# Inductive.net
KiCad netlist of a schematic drawn in Altium Designer
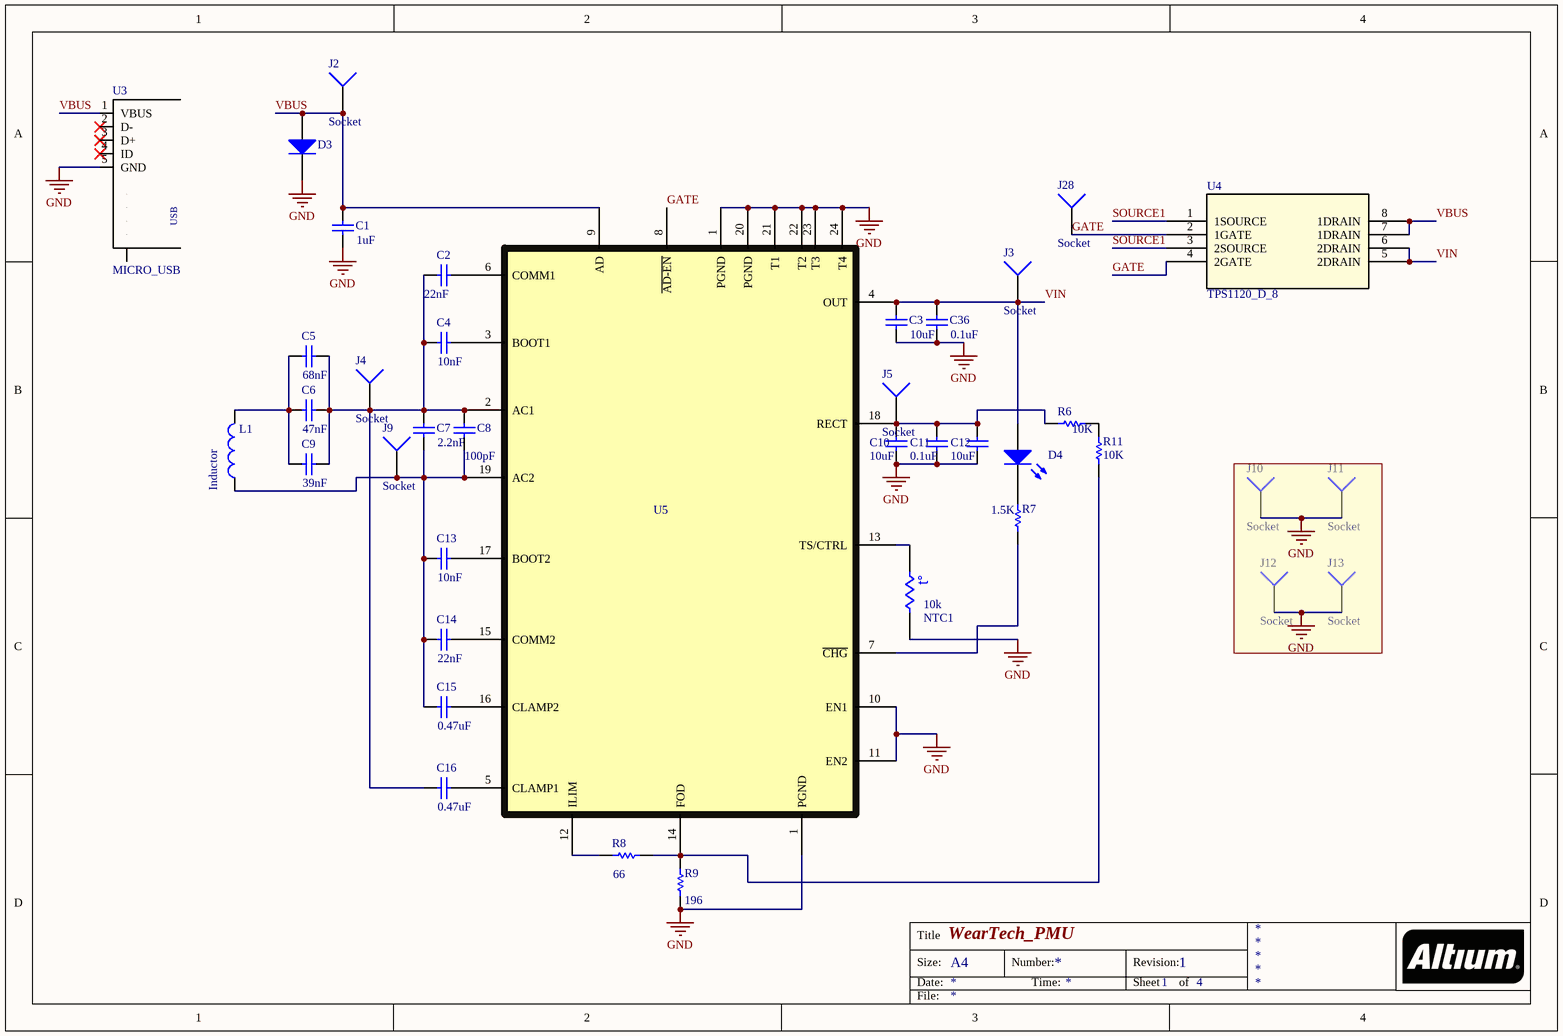
[diagram p0: Inductive.SchDoc]

(export (version "E")
  (design (tool "Eeschema 10.0.6"))
  (components
    (comp (ref "C1")
      (value "1uF")
      (footprint "1608[0603]")
      (description "CAP CER 1UF 6.3V X5R 0603")
      (fields (field (name "MANUFACTURE PART NUMBER") "C0603C105K9PACTU"))
      (libsource (lib "Miscellaneous Devices") (part "Cap"))
    )
    (comp (ref "C2")
      (value "22nF")
      (footprint "1608[0603]")
      (description "CAP CER 0.022UF 25V X7R 0603")
      (fields (field (name "MANUFACTURE PART NUMBER") "CL10B223KA8NNWC"))
      (libsource (lib "Miscellaneous Devices") (part "Cap"))
    )
    (comp (ref "C3")
      (value "10uF")
      (footprint "1608[0603]")
      (description "CAP CER 10UF 6.3V X5R 0603")
      (fields (field (name "MANUFACTURE PART NUMBER") "GRM188R60J106ME47D"))
      (libsource (lib "Miscellaneous Devices") (part "Cap"))
    )
    (comp (ref "C4")
      (value "10nF")
      (footprint "1608[0603]")
      (description "CAP CER 10000PF 25V X7R 0603")
      (fields (field (name "MANUFACTURE PART NUMBER") "CL10B103KA8NNNC"))
      (libsource (lib "Miscellaneous Devices") (part "Cap"))
    )
    (comp (ref "C5")
      (value "68nF")
      (footprint "1608[0603]")
      (description "GRM188R71E683KA01D")
      (fields (field (name "MANUFACTURE PART NUMBER") "CAP CER 0.068UF 25V X7R 0603"))
      (libsource (lib "Miscellaneous Devices") (part "Cap"))
    )
    (comp (ref "C6")
      (value "47nF")
      (footprint "1608[0603]")
      (description "CAP CER 0.047UF 25V X7R 0603")
      (fields (field (name "MANUFACTURE PART NUMBER") "CL10B473KA8NFNC"))
      (libsource (lib "Miscellaneous Devices") (part "Cap"))
    )
    (comp (ref "C7")
      (value "2.2nF")
      (footprint "1608[0603]")
      (description "CAP CER 2200PF 25V X7R 0603")
      (fields (field (name "MANUFACTURE PART NUMBER") "C0603C222K3RACTU"))
      (libsource (lib "Miscellaneous Devices") (part "Cap"))
    )
    (comp (ref "C8")
      (value "100pF")
      (footprint "1608[0603]")
      (description "CAP CER 0.1UF 25V X7R 0603")
      (fields (field (name "MANUFACTURE PART NUMBER") "C0603C104K3RACTU"))
      (libsource (lib "Miscellaneous Devices") (part "Cap"))
    )
    (comp (ref "C9")
      (value "39nF")
      (footprint "1608[0603]")
      (description "CAP CER 0.039UF 25V X7R 0603")
      (fields (field (name "MANUFACTURE PART NUMBER") "C0603C393K3RACTU"))
      (libsource (lib "Miscellaneous Devices") (part "Cap"))
    )
    (comp (ref "C10")
      (value "10uF")
      (footprint "1608[0603]")
      (description "CAP CER 10UF 16V X5R 0603")
      (fields (field (name "MANUFACTURE PART NUMBER") "GRM188R61C106KAALD"))
      (libsource (lib "Miscellaneous Devices") (part "Cap"))
    )
    (comp (ref "C11")
      (value "0.1uF")
      (footprint "1608[0603]")
      (description "0603YC104JAT2A")
      (fields (field (name "MANUFACTURE PART NUMBER") "CAP CER 0.1UF 16V X7R 0603"))
      (libsource (lib "Miscellaneous Devices") (part "Cap"))
    )
    (comp (ref "C12")
      (value "10uF")
      (footprint "1608[0603]")
      (description "CAP CER 10UF 16V X5R 0603")
      (fields (field (name "MANUFACTURE PART NUMBER") "GRM188R61C106KAALD"))
      (libsource (lib "Miscellaneous Devices") (part "Cap"))
    )
    (comp (ref "C13")
      (value "10nF")
      (footprint "1608[0603]")
      (description "CAP CER 10000PF 25V X7R 0603")
      (fields (field (name "MANUFACTURE PART NUMBER") "CL10B103KA8NNNC"))
      (libsource (lib "Miscellaneous Devices") (part "Cap"))
    )
    (comp (ref "C14")
      (value "22nF")
      (footprint "1608[0603]")
      (description "CAP CER 0.022UF 25V X7R 0603")
      (fields (field (name "MANUFACTURE PART NUMBER") "CL10B223KA8NNWC"))
      (libsource (lib "Miscellaneous Devices") (part "Cap"))
    )
    (comp (ref "C15")
      (value "0.47uF")
      (footprint "1608[0603]")
      (description "GRM188R71E474KA12D")
      (fields (field (name "MANUFACTURE PART NUMBER") "CAP CER 0.47UF 25V X7R 0603"))
      (libsource (lib "Miscellaneous Devices") (part "Cap"))
    )
    (comp (ref "C16")
      (value "0.47uF")
      (footprint "1608[0603]")
      (description "CAP CER 0.47UF 25V X7R 0603")
      (fields (field (name "MANUFACTURE PART NUMBER") "GRM188R71E474KA12D"))
      (libsource (lib "Miscellaneous Devices") (part "Cap"))
    )
    (comp (ref "C36")
      (value "0.1uF")
      (footprint "1608[0603]")
      (description "CAP CER 0.1UF 6.3V X7R 0603")
      (fields (field (name "MANUFACTURE PART NUMBER") "GRM188R70J104KA01D"))
      (libsource (lib "Miscellaneous Devices") (part "Cap"))
    )
    (comp (ref "D3")
      (value "Diode")
      (footprint "1608[0603]")
      (description "TVS DIODE 5VWM 12.5VC SC88")
      (fields (field (name "MANUFACTURE PART NUMBER") "SMF05CT1G"))
      (libsource (lib "Miscellaneous Devices") (part "Diode"))
    )
    (comp (ref "D4")
      (value "LED0")
      (footprint "1608[0603]")
      (description "LED ORANGE DIFFUSED 0603 SMD")
      (fields (field (name "MANUFACTURE PART NUMBER") "LO L29K-H2K1-24-Z"))
      (libsource (lib "Miscellaneous Devices") (part "LED0"))
    )
    (comp (ref "J2")
      (value "Socket")
      (footprint "PIN1")
      (description "Description")
      (fields
        (field (name "MANUFACTURE PART NUMBER") "68000-200HLF")
        (field (name "DIGI-KEY PART NUMBER") "609-5099-1-ND")
      )
      (libsource (lib "Miscellaneous Connectors") (part "Socket"))
    )
    (comp (ref "J3")
      (value "Socket")
      (footprint "PIN1")
      (description "Description")
      (fields
        (field (name "MANUFACTURE PART NUMBER") "68000-200HLF")
        (field (name "DIGI-KEY PART NUMBER") "609-5099-1-ND")
      )
      (libsource (lib "Miscellaneous Connectors") (part "Socket"))
    )
    (comp (ref "J4")
      (value "Socket")
      (footprint "PIN1")
      (description "Description")
      (fields
        (field (name "MANUFACTURE PART NUMBER") "68000-200HLF")
        (field (name "DIGI-KEY PART NUMBER") "609-5099-1-ND")
      )
      (libsource (lib "Miscellaneous Connectors") (part "Socket"))
    )
    (comp (ref "J5")
      (value "Socket")
      (footprint "PIN1")
      (description "Description")
      (fields
        (field (name "MANUFACTURE PART NUMBER") "68000-200HLF")
        (field (name "DIGI-KEY PART NUMBER") "609-5099-1-ND")
      )
      (libsource (lib "Miscellaneous Connectors") (part "Socket"))
    )
    (comp (ref "J9")
      (value "Socket")
      (footprint "PIN1")
      (description "Description")
      (fields
        (field (name "MANUFACTURE PART NUMBER") "68000-200HLF")
        (field (name "DIGI-KEY PART NUMBER") "609-5099-1-ND")
      )
      (libsource (lib "Miscellaneous Connectors") (part "Socket"))
    )
    (comp (ref "J10")
      (value "Socket")
      (footprint "PIN1")
      (description "Description")
      (fields
        (field (name "MANUFACTURE PART NUMBER") "68000-200HLF")
        (field (name "DIGI-KEY PART NUMBER") "609-5099-1-ND")
      )
      (libsource (lib "Miscellaneous Connectors") (part "Socket"))
    )
    (comp (ref "J11")
      (value "Socket")
      (footprint "PIN1")
      (description "Description")
      (fields
        (field (name "MANUFACTURE PART NUMBER") "68000-200HLF")
        (field (name "DIGI-KEY PART NUMBER") "609-5099-1-ND")
      )
      (libsource (lib "Miscellaneous Connectors") (part "Socket"))
    )
    (comp (ref "J12")
      (value "Socket")
      (footprint "PIN1")
      (description "Description")
      (fields
        (field (name "MANUFACTURE PART NUMBER") "68000-200HLF")
        (field (name "DIGI-KEY PART NUMBER") "609-5099-1-ND")
      )
      (libsource (lib "Miscellaneous Connectors") (part "Socket"))
    )
    (comp (ref "J13")
      (value "Socket")
      (footprint "PIN1")
      (description "Description")
      (fields
        (field (name "MANUFACTURE PART NUMBER") "68000-200HLF")
        (field (name "DIGI-KEY PART NUMBER") "609-5099-1-ND")
      )
      (libsource (lib "Miscellaneous Connectors") (part "Socket"))
    )
    (comp (ref "J28")
      (value "Socket")
      (footprint "PIN1")
      (description "Description")
      (fields
        (field (name "MANUFACTURE PART NUMBER") "68000-200HLF")
        (field (name "DIGI-KEY PART NUMBER") "609-5099-1-ND")
      )
      (libsource (lib "Miscellaneous Connectors") (part "Socket"))
    )
    (comp (ref "L1")
      (value "Inductor")
      (footprint "1608[0603]")
      (description "RX 1 COIL 1 LAYER 10.7UH")
      (fields
        (field (name "MANUFACTURE PART NUMBER") "Manufacture Part Number")
        (field (name "DIGI-KEY PART NUMBER") "541-1695-ND")
      )
      (libsource (lib "Miscellaneous Devices") (part "Inductor"))
    )
    (comp (ref "NTC1")
      (value "10k")
      (footprint "1608[0603]")
      (description "RC0603JR-0710KL")
      (fields (field (name "DIGI-KEY PART NUMBER") "311-10KGRCT-ND"))
      (libsource (lib "Miscellaneous Devices") (part "Res Thermal"))
    )
    (comp (ref "R6")
      (value "10K")
      (footprint "1608[0603]")
      (description "RES SMD 10K OHM 5% 1/10W 0603")
      (fields (field (name "MANUFACTURE PART NUMBER") "RC0603JR-0710KL"))
      (libsource (lib "Miscellaneous Devices") (part "Res1"))
    )
    (comp (ref "R7")
      (value "1.5K")
      (footprint "1608[0603]")
      (description "RES SMD 1.5K OHM 5% 1/10W 0603")
      (fields (field (name "MANUFACTURE PART NUMBER") "RC0603JR-071K5L"))
      (libsource (lib "Miscellaneous Devices") (part "Res1"))
    )
    (comp (ref "R8")
      (value "66")
      (footprint "1608[0603]")
      (description "RES SMD 66.5 OHM 1% 1/10W 0603")
      (fields (field (name "MANUFACTURE PART NUMBER") "RC0603FR-0766R5L"))
      (libsource (lib "Miscellaneous Devices") (part "Res1"))
    )
    (comp (ref "R9")
      (value "196")
      (footprint "1608[0603]")
      (description "RES SMD 196 OHM 1% 1/10W 0603")
      (fields (field (name "MANUFACTURE PART NUMBER") "RC0603FR-07196RL"))
      (libsource (lib "Miscellaneous Devices") (part "Res1"))
    )
    (comp (ref "R11")
      (value "10K")
      (footprint "1608[0603]")
      (description "RES SMD 10K OHM 5% 1/10W 0603")
      (fields (field (name "MANUFACTURE PART NUMBER") "RC0603JR-0710KL"))
      (libsource (lib "Miscellaneous Devices") (part "Res1"))
    )
    (comp (ref "U3")
      (value "MICRO_USB")
      (footprint "MICRO USB")
      (description "CONN USB MICRO B RECPT SMT R/A")
      (fields
        (field (name "MANUFACTURE PART NUMBER") "10118192-0001LF")
        (field (name "DIGI-KEY PART NUMBER") "609-4613-1-ND")
      )
      (libsource (lib "WearTechSchLib") (part "MICRO_USB"))
    )
    (comp (ref "U4")
      (value "TPS1120_D_8")
      (footprint "BlockSwitch")
      (description "Description")
      (fields
        (field (name "MANUFACTURE PART NUMBER") "Manufacture Part Number")
        (field (name "DIGI-KEY PART NUMBER") "296-1352-1-ND")
      )
      (libsource (lib "WearTechSchLib") (part "TPS1120_D_8"))
    )
    (comp (ref "U5")
      (value "BQ51013B")
      (footprint "BQ51013B")
      (description "IC WIRELESS PWR RCVR 20QFN")
      (fields
        (field (name "MANUFACTURE PART NUMBER") "BQ51013BRHLR")
        (field (name "DIGI-KEY PART NUMBER") "296-38885-1-ND")
      )
      (libsource (lib "WearTechSchLib") (part "BQ51013B"))
    )
  )
  (nets
    (net (code "1") (name "/GATE") (class "Default")
      (node (ref "J28") (pin "1") (pinfunction "1_1") (pintype "passive"))
      (node (ref "U4") (pin "2") (pinfunction "1GATE_2") (pintype "passive"))
      (node (ref "U4") (pin "4") (pinfunction "2GATE_4") (pintype "passive"))
      (node (ref "U5") (pin "8") (pinfunction "~{AD-EN}_8") (pintype "passive"))
    )
    (net (code "2") (name "/SOURCE1") (class "Default")
      (node (ref "U4") (pin "1") (pinfunction "1SOURCE_1") (pintype "passive"))
      (node (ref "U4") (pin "3") (pinfunction "2SOURCE_3") (pintype "passive"))
    )
    (net (code "3") (name "/VBUS") (class "Default")
      (node (ref "C1") (pin "2") (pinfunction "2_2") (pintype "passive"))
      (node (ref "D3") (pin "1") (pinfunction "A_1") (pintype "passive"))
      (node (ref "J2") (pin "1") (pinfunction "1_1") (pintype "passive"))
      (node (ref "U3") (pin "1") (pinfunction "VBUS_1") (pintype "passive"))
      (node (ref "U4") (pin "7") (pinfunction "1DRAIN_7") (pintype "passive"))
      (node (ref "U4") (pin "8") (pinfunction "1DRAIN_8") (pintype "passive"))
      (node (ref "U5") (pin "9") (pinfunction "AD_9") (pintype "passive"))
    )
    (net (code "4") (name "/VIN") (class "Default")
      (node (ref "C3") (pin "1") (pinfunction "1_1") (pintype "passive"))
      (node (ref "C36") (pin "1") (pinfunction "1_1") (pintype "passive"))
      (node (ref "D4") (pin "1") (pinfunction "A_1") (pintype "passive"))
      (node (ref "J3") (pin "1") (pinfunction "1_1") (pintype "passive"))
      (node (ref "U4") (pin "5") (pinfunction "2DRAIN_5") (pintype "passive"))
      (node (ref "U4") (pin "6") (pinfunction "2DRAIN_6") (pintype "passive"))
      (node (ref "U5") (pin "4") (pinfunction "OUT_4") (pintype "passive"))
    )
    (net (code "5") (name "GND") (class "Default")
      (node (ref "C1") (pin "1") (pinfunction "1_1") (pintype "passive"))
      (node (ref "C10") (pin "2") (pinfunction "2_2") (pintype "passive"))
      (node (ref "C11") (pin "2") (pinfunction "2_2") (pintype "passive"))
      (node (ref "C12") (pin "2") (pinfunction "2_2") (pintype "passive"))
      (node (ref "C3") (pin "2") (pinfunction "2_2") (pintype "passive"))
      (node (ref "C36") (pin "2") (pinfunction "2_2") (pintype "passive"))
      (node (ref "D3") (pin "2") (pinfunction "K_2") (pintype "passive"))
      (node (ref "J10") (pin "1") (pinfunction "1_1") (pintype "passive"))
      (node (ref "J11") (pin "1") (pinfunction "1_1") (pintype "passive"))
      (node (ref "J12") (pin "1") (pinfunction "1_1") (pintype "passive"))
      (node (ref "J13") (pin "1") (pinfunction "1_1") (pintype "passive"))
      (node (ref "NTC1") (pin "2") (pinfunction "2_2") (pintype "passive"))
      (node (ref "R9") (pin "2") (pinfunction "2_2") (pintype "passive"))
      (node (ref "U3") (pin "5") (pinfunction "GND_5") (pintype "passive"))
      (node (ref "U5") (pin "1") (pinfunction "PGND_1") (pintype "passive"))
      (node (ref "U5") (pin "10") (pinfunction "EN1_10") (pintype "passive"))
      (node (ref "U5") (pin "11") (pinfunction "EN2_11") (pintype "passive"))
      (node (ref "U5") (pin "20") (pinfunction "PGND_20") (pintype "passive"))
      (node (ref "U5") (pin "21") (pinfunction "T1_21") (pintype "passive"))
      (node (ref "U5") (pin "22") (pinfunction "T2_22") (pintype "passive"))
      (node (ref "U5") (pin "23") (pinfunction "T3_23") (pintype "passive"))
      (node (ref "U5") (pin "24") (pinfunction "T4_24") (pintype "passive"))
    )
    (net (code "6") (name "Net-(C5-Pad2)") (class "Default")
      (node (ref "C5") (pin "2") (pinfunction "2_2") (pintype "passive"))
      (node (ref "C6") (pin "2") (pinfunction "2_2") (pintype "passive"))
      (node (ref "C9") (pin "2") (pinfunction "2_2") (pintype "passive"))
      (node (ref "L1") (pin "2") (pinfunction "2_2") (pintype "passive"))
    )
    (net (code "7") (name "Net-(D4-K)") (class "Default")
      (node (ref "D4") (pin "2") (pinfunction "K_2") (pintype "passive"))
      (node (ref "R7") (pin "1") (pinfunction "1_1") (pintype "passive"))
    )
    (net (code "8") (name "Net-(R11-Pad2)") (class "Default")
      (node (ref "R11") (pin "2") (pinfunction "2_2") (pintype "passive"))
      (node (ref "R6") (pin "2") (pinfunction "2_2") (pintype "passive"))
    )
    (net (code "9") (name "Net-(U5-AC1)") (class "Default")
      (node (ref "C16") (pin "2") (pinfunction "2_2") (pintype "passive"))
      (node (ref "C2") (pin "2") (pinfunction "2_2") (pintype "passive"))
      (node (ref "C4") (pin "2") (pinfunction "2_2") (pintype "passive"))
      (node (ref "C5") (pin "1") (pinfunction "1_1") (pintype "passive"))
      (node (ref "C6") (pin "1") (pinfunction "1_1") (pintype "passive"))
      (node (ref "C7") (pin "1") (pinfunction "1_1") (pintype "passive"))
      (node (ref "C8") (pin "1") (pinfunction "1_1") (pintype "passive"))
      (node (ref "C9") (pin "1") (pinfunction "1_1") (pintype "passive"))
      (node (ref "J4") (pin "1") (pinfunction "1_1") (pintype "passive"))
      (node (ref "U5") (pin "2") (pinfunction "AC1_2") (pintype "passive"))
    )
    (net (code "10") (name "Net-(U5-AC2)") (class "Default")
      (node (ref "C13") (pin "2") (pinfunction "2_2") (pintype "passive"))
      (node (ref "C14") (pin "2") (pinfunction "2_2") (pintype "passive"))
      (node (ref "C15") (pin "2") (pinfunction "2_2") (pintype "passive"))
      (node (ref "C7") (pin "2") (pinfunction "2_2") (pintype "passive"))
      (node (ref "C8") (pin "2") (pinfunction "2_2") (pintype "passive"))
      (node (ref "J9") (pin "1") (pinfunction "1_1") (pintype "passive"))
      (node (ref "L1") (pin "1") (pinfunction "1_1") (pintype "passive"))
      (node (ref "U5") (pin "19") (pinfunction "AC2_19") (pintype "passive"))
    )
    (net (code "11") (name "Net-(U5-BOOT1)") (class "Default")
      (node (ref "C4") (pin "1") (pinfunction "1_1") (pintype "passive"))
      (node (ref "U5") (pin "3") (pinfunction "BOOT1_3") (pintype "passive"))
    )
    (net (code "12") (name "Net-(U5-BOOT2)") (class "Default")
      (node (ref "C13") (pin "1") (pinfunction "1_1") (pintype "passive"))
      (node (ref "U5") (pin "17") (pinfunction "BOOT2_17") (pintype "passive"))
    )
    (net (code "13") (name "Net-(U5-CLAMP1)") (class "Default")
      (node (ref "C16") (pin "1") (pinfunction "1_1") (pintype "passive"))
      (node (ref "U5") (pin "5") (pinfunction "CLAMP1_5") (pintype "passive"))
    )
    (net (code "14") (name "Net-(U5-CLAMP2)") (class "Default")
      (node (ref "C15") (pin "1") (pinfunction "1_1") (pintype "passive"))
      (node (ref "U5") (pin "16") (pinfunction "CLAMP2_16") (pintype "passive"))
    )
    (net (code "15") (name "Net-(U5-COMM1)") (class "Default")
      (node (ref "C2") (pin "1") (pinfunction "1_1") (pintype "passive"))
      (node (ref "U5") (pin "6") (pinfunction "COMM1_6") (pintype "passive"))
    )
    (net (code "16") (name "Net-(U5-COMM2)") (class "Default")
      (node (ref "C14") (pin "1") (pinfunction "1_1") (pintype "passive"))
      (node (ref "U5") (pin "15") (pinfunction "COMM2_15") (pintype "passive"))
    )
    (net (code "17") (name "Net-(U5-FOD)") (class "Default")
      (node (ref "R11") (pin "1") (pinfunction "1_1") (pintype "passive"))
      (node (ref "R8") (pin "2") (pinfunction "2_2") (pintype "passive"))
      (node (ref "R9") (pin "1") (pinfunction "1_1") (pintype "passive"))
      (node (ref "U5") (pin "14") (pinfunction "FOD_14") (pintype "passive"))
    )
    (net (code "18") (name "Net-(U5-ILIM)") (class "Default")
      (node (ref "R8") (pin "1") (pinfunction "1_1") (pintype "passive"))
      (node (ref "U5") (pin "12") (pinfunction "ILIM_12") (pintype "passive"))
    )
    (net (code "19") (name "Net-(U5-RECT)") (class "Default")
      (node (ref "C10") (pin "1") (pinfunction "1_1") (pintype "passive"))
      (node (ref "C11") (pin "1") (pinfunction "1_1") (pintype "passive"))
      (node (ref "C12") (pin "1") (pinfunction "1_1") (pintype "passive"))
      (node (ref "J5") (pin "1") (pinfunction "1_1") (pintype "passive"))
      (node (ref "R6") (pin "1") (pinfunction "1_1") (pintype "passive"))
      (node (ref "U5") (pin "18") (pinfunction "RECT_18") (pintype "passive"))
    )
    (net (code "20") (name "Net-(U5-TS{slash}CTRL)") (class "Default")
      (node (ref "NTC1") (pin "1") (pinfunction "1_1") (pintype "passive"))
      (node (ref "U5") (pin "13") (pinfunction "TS/CTRL_13") (pintype "passive"))
    )
    (net (code "21") (name "Net-(U5-~{CHG})") (class "Default")
      (node (ref "R7") (pin "2") (pinfunction "2_2") (pintype "passive"))
      (node (ref "U5") (pin "7") (pinfunction "~{CHG}_7") (pintype "passive"))
    )
    (net (code "22") (name "unconnected-(U3-D+-Pad3)") (class "Default")
      (node (ref "U3") (pin "3") (pinfunction "D+_3") (pintype "passive+no_connect"))
    )
    (net (code "23") (name "unconnected-(U3-D--Pad2)") (class "Default")
      (node (ref "U3") (pin "2") (pinfunction "D-_2") (pintype "passive+no_connect"))
    )
    (net (code "24") (name "unconnected-(U3-ID-Pad4)") (class "Default")
      (node (ref "U3") (pin "4") (pinfunction "ID_4") (pintype "passive+no_connect"))
    )
    (net (code "25") (name "unconnected-(U3-S-PadM1)") (class "Default")
      (node (ref "U3") (pin "M1") (pinfunction "S_M1") (pintype "passive"))
    )
    (net (code "26") (name "unconnected-(U3-S-PadM2)") (class "Default")
      (node (ref "U3") (pin "M2") (pinfunction "S_M2") (pintype "passive"))
    )
    (net (code "27") (name "unconnected-(U3-S-PadS1)") (class "Default")
      (node (ref "U3") (pin "S1") (pinfunction "S_S1") (pintype "passive"))
    )
    (net (code "28") (name "unconnected-(U3-S-PadS2)") (class "Default")
      (node (ref "U3") (pin "S2") (pinfunction "S_S2") (pintype "passive"))
    )
    (net (code "29") (name "unconnected-(U3-S-PadS3)") (class "Default")
      (node (ref "U3") (pin "S3") (pinfunction "S_S3") (pintype "passive"))
    )
    (net (code "30") (name "unconnected-(U3-S-PadS4)") (class "Default")
      (node (ref "U3") (pin "S4") (pinfunction "S_S4") (pintype "passive"))
    )
  )
)
